# elysium_v0_3.net
KiCad netlist of a schematic drawn in EAGLE
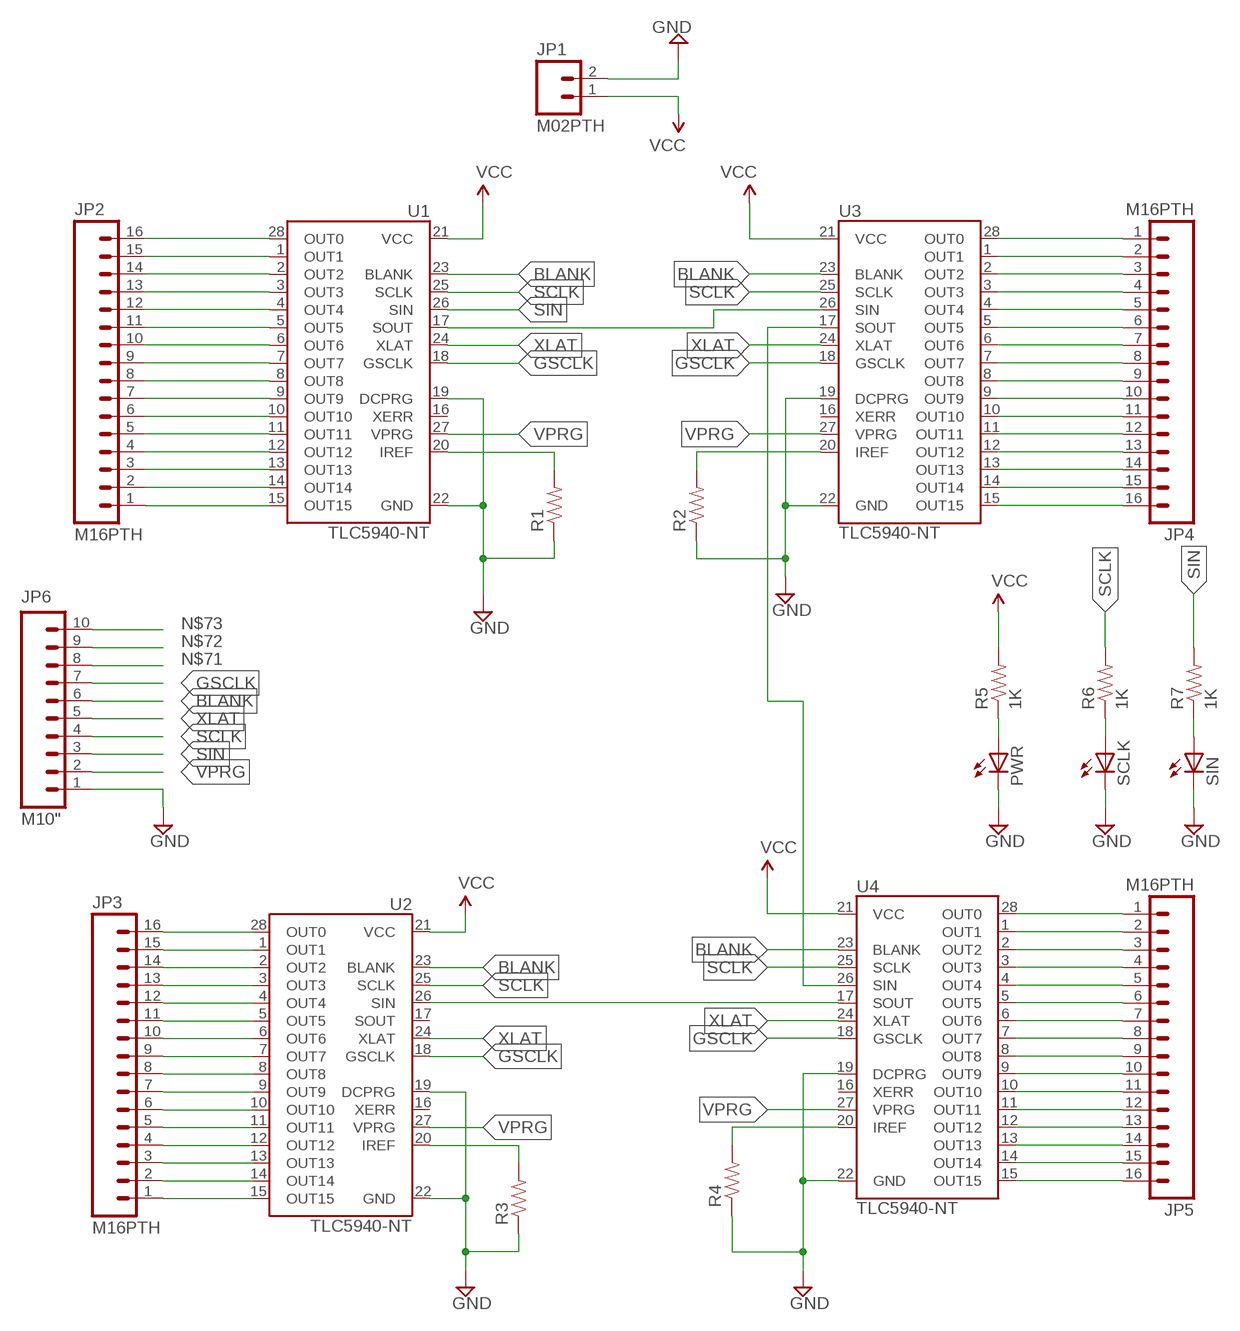
[diagram p0: schematic, sheet 1]

(export (version "E")
  (design (tool "Eeschema 10.0.6"))
  (components
    (comp (ref "JP1")
      (value "M02PTH")
      (footprint "eagle-import:1X02")
      (libsource (lib "eagle-import") (part "M02PTH"))
    )
    (comp (ref "JP2")
      (value "M16PTH")
      (footprint "eagle-import:1X16")
      (libsource (lib "eagle-import") (part "M16PTH"))
    )
    (comp (ref "JP3")
      (value "M16PTH")
      (footprint "eagle-import:1X16")
      (libsource (lib "eagle-import") (part "M16PTH"))
    )
    (comp (ref "JP4")
      (value "M16PTH")
      (footprint "eagle-import:1X16")
      (libsource (lib "eagle-import") (part "M16PTH"))
    )
    (comp (ref "JP5")
      (value "M16PTH")
      (footprint "eagle-import:1X16")
      (libsource (lib "eagle-import") (part "M16PTH"))
    )
    (comp (ref "JP6")
      (value "M10\"")
      (footprint "eagle-import:1X10")
      (libsource (lib "eagle-import") (part "M10{dblquote}"))
    )
    (comp (ref "PWR")
      (value "LED5MM")
      (footprint "eagle-import:LED5MM")
      (libsource (lib "eagle-import") (part "LED5MM"))
    )
    (comp (ref "R1")
      (value "RESISTOREZ")
      (footprint "eagle-import:AXIAL-0.3EZ")
      (libsource (lib "eagle-import") (part "RESISTOREZ"))
    )
    (comp (ref "R2")
      (value "RESISTOREZ")
      (footprint "eagle-import:AXIAL-0.3EZ")
      (libsource (lib "eagle-import") (part "RESISTOREZ"))
    )
    (comp (ref "R3")
      (value "RESISTOREZ")
      (footprint "eagle-import:AXIAL-0.3EZ")
      (libsource (lib "eagle-import") (part "RESISTOREZ"))
    )
    (comp (ref "R4")
      (value "RESISTOREZ")
      (footprint "eagle-import:AXIAL-0.3EZ")
      (libsource (lib "eagle-import") (part "RESISTOREZ"))
    )
    (comp (ref "R5")
      (value "1K")
      (footprint "eagle-import:AXIAL-0.3EZ")
      (libsource (lib "eagle-import") (part "RESISTOREZ"))
    )
    (comp (ref "R6")
      (value "1K")
      (footprint "eagle-import:AXIAL-0.3EZ")
      (libsource (lib "eagle-import") (part "RESISTOREZ"))
    )
    (comp (ref "R7")
      (value "1K")
      (footprint "eagle-import:AXIAL-0.3EZ")
      (libsource (lib "eagle-import") (part "RESISTOREZ"))
    )
    (comp (ref "SCLK")
      (value "LED5MM")
      (footprint "eagle-import:LED5MM")
      (libsource (lib "eagle-import") (part "LED5MM"))
    )
    (comp (ref "SIN")
      (value "LED5MM")
      (footprint "eagle-import:LED5MM")
      (libsource (lib "eagle-import") (part "LED5MM"))
    )
    (comp (ref "U1")
      (value "TLC5940-NT")
      (footprint "eagle-import:DIL28-3")
      (libsource (lib "eagle-import") (part "TLC5940-NT"))
    )
    (comp (ref "U2")
      (value "TLC5940-NT")
      (footprint "eagle-import:DIL28-3")
      (libsource (lib "eagle-import") (part "TLC5940-NT"))
    )
    (comp (ref "U3")
      (value "TLC5940-NT")
      (footprint "eagle-import:DIL28-3")
      (libsource (lib "eagle-import") (part "TLC5940-NT"))
    )
    (comp (ref "U4")
      (value "TLC5940-NT")
      (footprint "eagle-import:DIL28-3")
      (libsource (lib "eagle-import") (part "TLC5940-NT"))
    )
  )
  (nets
    (net (code "1") (name "/N$71") (class "Default")
      (node (ref "JP6") (pin "8") (pinfunction "8_8") (pintype "passive"))
    )
    (net (code "2") (name "/N$72") (class "Default")
      (node (ref "JP6") (pin "9") (pinfunction "9_9") (pintype "passive"))
    )
    (net (code "3") (name "/N$73") (class "Default")
      (node (ref "JP6") (pin "10") (pinfunction "10_10") (pintype "passive"))
    )
    (net (code "4") (name "BLANK") (class "Default")
      (node (ref "JP6") (pin "6") (pinfunction "6_6") (pintype "passive"))
      (node (ref "U1") (pin "23") (pinfunction "BLANK_23") (pintype "bidirectional"))
      (node (ref "U2") (pin "23") (pinfunction "BLANK_23") (pintype "bidirectional"))
      (node (ref "U3") (pin "23") (pinfunction "BLANK_23") (pintype "bidirectional"))
      (node (ref "U4") (pin "23") (pinfunction "BLANK_23") (pintype "bidirectional"))
    )
    (net (code "5") (name "GND") (class "Default")
      (node (ref "JP1") (pin "2") (pinfunction "2_2") (pintype "passive"))
      (node (ref "JP6") (pin "1") (pinfunction "1_1") (pintype "passive"))
      (node (ref "PWR") (pin "K") (pinfunction "C_K") (pintype "passive"))
      (node (ref "R1") (pin "P$1") (pinfunction "1_P$1") (pintype "passive"))
      (node (ref "R2") (pin "P$1") (pinfunction "1_P$1") (pintype "passive"))
      (node (ref "R3") (pin "P$1") (pinfunction "1_P$1") (pintype "passive"))
      (node (ref "R4") (pin "P$1") (pinfunction "1_P$1") (pintype "passive"))
      (node (ref "SCLK") (pin "K") (pinfunction "C_K") (pintype "passive"))
      (node (ref "SIN") (pin "K") (pinfunction "C_K") (pintype "passive"))
      (node (ref "U1") (pin "19") (pinfunction "DCPRG_19") (pintype "bidirectional"))
      (node (ref "U1") (pin "22") (pinfunction "GND_22") (pintype "bidirectional"))
      (node (ref "U2") (pin "19") (pinfunction "DCPRG_19") (pintype "bidirectional"))
      (node (ref "U2") (pin "22") (pinfunction "GND_22") (pintype "bidirectional"))
      (node (ref "U3") (pin "19") (pinfunction "DCPRG_19") (pintype "bidirectional"))
      (node (ref "U3") (pin "22") (pinfunction "GND_22") (pintype "bidirectional"))
      (node (ref "U4") (pin "19") (pinfunction "DCPRG_19") (pintype "bidirectional"))
      (node (ref "U4") (pin "22") (pinfunction "GND_22") (pintype "bidirectional"))
    )
    (net (code "6") (name "GSCLK") (class "Default")
      (node (ref "JP6") (pin "7") (pinfunction "7_7") (pintype "passive"))
      (node (ref "U1") (pin "18") (pinfunction "GSCLK_18") (pintype "bidirectional"))
      (node (ref "U2") (pin "18") (pinfunction "GSCLK_18") (pintype "bidirectional"))
      (node (ref "U3") (pin "18") (pinfunction "GSCLK_18") (pintype "bidirectional"))
      (node (ref "U4") (pin "18") (pinfunction "GSCLK_18") (pintype "bidirectional"))
    )
    (net (code "7") (name "Net-(R1-2)") (class "Default")
      (node (ref "R1") (pin "P$2") (pinfunction "2_P$2") (pintype "passive"))
      (node (ref "U1") (pin "20") (pinfunction "IREF_20") (pintype "bidirectional"))
    )
    (net (code "8") (name "Net-(R2-2)") (class "Default")
      (node (ref "R2") (pin "P$2") (pinfunction "2_P$2") (pintype "passive"))
      (node (ref "U3") (pin "20") (pinfunction "IREF_20") (pintype "bidirectional"))
    )
    (net (code "9") (name "Net-(R3-2)") (class "Default")
      (node (ref "R3") (pin "P$2") (pinfunction "2_P$2") (pintype "passive"))
      (node (ref "U2") (pin "20") (pinfunction "IREF_20") (pintype "bidirectional"))
    )
    (net (code "10") (name "Net-(R4-2)") (class "Default")
      (node (ref "R4") (pin "P$2") (pinfunction "2_P$2") (pintype "passive"))
      (node (ref "U4") (pin "20") (pinfunction "IREF_20") (pintype "bidirectional"))
    )
    (net (code "11") (name "Net-(R5-1)") (class "Default")
      (node (ref "PWR") (pin "A") (pinfunction "A_A") (pintype "passive"))
      (node (ref "R5") (pin "P$1") (pinfunction "1_P$1") (pintype "passive"))
    )
    (net (code "12") (name "Net-(R6-1)") (class "Default")
      (node (ref "R6") (pin "P$1") (pinfunction "1_P$1") (pintype "passive"))
      (node (ref "SCLK") (pin "A") (pinfunction "A_A") (pintype "passive"))
    )
    (net (code "13") (name "Net-(R7-1)") (class "Default")
      (node (ref "R7") (pin "P$1") (pinfunction "1_P$1") (pintype "passive"))
      (node (ref "SIN") (pin "A") (pinfunction "A_A") (pintype "passive"))
    )
    (net (code "14") (name "Net-(U1-OUT0)") (class "Default")
      (node (ref "JP2") (pin "16") (pinfunction "16_16") (pintype "passive"))
      (node (ref "U1") (pin "28") (pinfunction "OUT0_28") (pintype "bidirectional"))
    )
    (net (code "15") (name "Net-(U1-OUT1)") (class "Default")
      (node (ref "JP2") (pin "15") (pinfunction "15_15") (pintype "passive"))
      (node (ref "U1") (pin "1") (pinfunction "OUT1_1") (pintype "bidirectional"))
    )
    (net (code "16") (name "Net-(U1-OUT2)") (class "Default")
      (node (ref "JP2") (pin "14") (pinfunction "14_14") (pintype "passive"))
      (node (ref "U1") (pin "2") (pinfunction "OUT2_2") (pintype "bidirectional"))
    )
    (net (code "17") (name "Net-(U1-OUT3)") (class "Default")
      (node (ref "JP2") (pin "13") (pinfunction "13_13") (pintype "passive"))
      (node (ref "U1") (pin "3") (pinfunction "OUT3_3") (pintype "bidirectional"))
    )
    (net (code "18") (name "Net-(U1-OUT4)") (class "Default")
      (node (ref "JP2") (pin "12") (pinfunction "12_12") (pintype "passive"))
      (node (ref "U1") (pin "4") (pinfunction "OUT4_4") (pintype "bidirectional"))
    )
    (net (code "19") (name "Net-(U1-OUT5)") (class "Default")
      (node (ref "JP2") (pin "11") (pinfunction "11_11") (pintype "passive"))
      (node (ref "U1") (pin "5") (pinfunction "OUT5_5") (pintype "bidirectional"))
    )
    (net (code "20") (name "Net-(U1-OUT6)") (class "Default")
      (node (ref "JP2") (pin "10") (pinfunction "10_10") (pintype "passive"))
      (node (ref "U1") (pin "6") (pinfunction "OUT6_6") (pintype "bidirectional"))
    )
    (net (code "21") (name "Net-(U1-OUT7)") (class "Default")
      (node (ref "JP2") (pin "9") (pinfunction "9_9") (pintype "passive"))
      (node (ref "U1") (pin "7") (pinfunction "OUT7_7") (pintype "bidirectional"))
    )
    (net (code "22") (name "Net-(U1-OUT8)") (class "Default")
      (node (ref "JP2") (pin "8") (pinfunction "8_8") (pintype "passive"))
      (node (ref "U1") (pin "8") (pinfunction "OUT8_8") (pintype "bidirectional"))
    )
    (net (code "23") (name "Net-(U1-OUT9)") (class "Default")
      (node (ref "JP2") (pin "7") (pinfunction "7_7") (pintype "passive"))
      (node (ref "U1") (pin "9") (pinfunction "OUT9_9") (pintype "bidirectional"))
    )
    (net (code "24") (name "Net-(U1-OUT10)") (class "Default")
      (node (ref "JP2") (pin "6") (pinfunction "6_6") (pintype "passive"))
      (node (ref "U1") (pin "10") (pinfunction "OUT10_10") (pintype "bidirectional"))
    )
    (net (code "25") (name "Net-(U1-OUT11)") (class "Default")
      (node (ref "JP2") (pin "5") (pinfunction "5_5") (pintype "passive"))
      (node (ref "U1") (pin "11") (pinfunction "OUT11_11") (pintype "bidirectional"))
    )
    (net (code "26") (name "Net-(U1-OUT12)") (class "Default")
      (node (ref "JP2") (pin "4") (pinfunction "4_4") (pintype "passive"))
      (node (ref "U1") (pin "12") (pinfunction "OUT12_12") (pintype "bidirectional"))
    )
    (net (code "27") (name "Net-(U1-OUT13)") (class "Default")
      (node (ref "JP2") (pin "3") (pinfunction "3_3") (pintype "passive"))
      (node (ref "U1") (pin "13") (pinfunction "OUT13_13") (pintype "bidirectional"))
    )
    (net (code "28") (name "Net-(U1-OUT14)") (class "Default")
      (node (ref "JP2") (pin "2") (pinfunction "2_2") (pintype "passive"))
      (node (ref "U1") (pin "14") (pinfunction "OUT14_14") (pintype "bidirectional"))
    )
    (net (code "29") (name "Net-(U1-OUT15)") (class "Default")
      (node (ref "JP2") (pin "1") (pinfunction "1_1") (pintype "passive"))
      (node (ref "U1") (pin "15") (pinfunction "OUT15_15") (pintype "bidirectional"))
    )
    (net (code "30") (name "Net-(U1-SOUT)") (class "Default")
      (node (ref "U1") (pin "17") (pinfunction "SOUT_17") (pintype "bidirectional"))
      (node (ref "U3") (pin "26") (pinfunction "SIN_26") (pintype "bidirectional"))
    )
    (net (code "31") (name "Net-(U2-OUT0)") (class "Default")
      (node (ref "JP3") (pin "16") (pinfunction "16_16") (pintype "passive"))
      (node (ref "U2") (pin "28") (pinfunction "OUT0_28") (pintype "bidirectional"))
    )
    (net (code "32") (name "Net-(U2-OUT1)") (class "Default")
      (node (ref "JP3") (pin "15") (pinfunction "15_15") (pintype "passive"))
      (node (ref "U2") (pin "1") (pinfunction "OUT1_1") (pintype "bidirectional"))
    )
    (net (code "33") (name "Net-(U2-OUT2)") (class "Default")
      (node (ref "JP3") (pin "14") (pinfunction "14_14") (pintype "passive"))
      (node (ref "U2") (pin "2") (pinfunction "OUT2_2") (pintype "bidirectional"))
    )
    (net (code "34") (name "Net-(U2-OUT3)") (class "Default")
      (node (ref "JP3") (pin "13") (pinfunction "13_13") (pintype "passive"))
      (node (ref "U2") (pin "3") (pinfunction "OUT3_3") (pintype "bidirectional"))
    )
    (net (code "35") (name "Net-(U2-OUT4)") (class "Default")
      (node (ref "JP3") (pin "12") (pinfunction "12_12") (pintype "passive"))
      (node (ref "U2") (pin "4") (pinfunction "OUT4_4") (pintype "bidirectional"))
    )
    (net (code "36") (name "Net-(U2-OUT5)") (class "Default")
      (node (ref "JP3") (pin "11") (pinfunction "11_11") (pintype "passive"))
      (node (ref "U2") (pin "5") (pinfunction "OUT5_5") (pintype "bidirectional"))
    )
    (net (code "37") (name "Net-(U2-OUT6)") (class "Default")
      (node (ref "JP3") (pin "10") (pinfunction "10_10") (pintype "passive"))
      (node (ref "U2") (pin "6") (pinfunction "OUT6_6") (pintype "bidirectional"))
    )
    (net (code "38") (name "Net-(U2-OUT7)") (class "Default")
      (node (ref "JP3") (pin "9") (pinfunction "9_9") (pintype "passive"))
      (node (ref "U2") (pin "7") (pinfunction "OUT7_7") (pintype "bidirectional"))
    )
    (net (code "39") (name "Net-(U2-OUT8)") (class "Default")
      (node (ref "JP3") (pin "8") (pinfunction "8_8") (pintype "passive"))
      (node (ref "U2") (pin "8") (pinfunction "OUT8_8") (pintype "bidirectional"))
    )
    (net (code "40") (name "Net-(U2-OUT9)") (class "Default")
      (node (ref "JP3") (pin "7") (pinfunction "7_7") (pintype "passive"))
      (node (ref "U2") (pin "9") (pinfunction "OUT9_9") (pintype "bidirectional"))
    )
    (net (code "41") (name "Net-(U2-OUT10)") (class "Default")
      (node (ref "JP3") (pin "6") (pinfunction "6_6") (pintype "passive"))
      (node (ref "U2") (pin "10") (pinfunction "OUT10_10") (pintype "bidirectional"))
    )
    (net (code "42") (name "Net-(U2-OUT11)") (class "Default")
      (node (ref "JP3") (pin "5") (pinfunction "5_5") (pintype "passive"))
      (node (ref "U2") (pin "11") (pinfunction "OUT11_11") (pintype "bidirectional"))
    )
    (net (code "43") (name "Net-(U2-OUT12)") (class "Default")
      (node (ref "JP3") (pin "4") (pinfunction "4_4") (pintype "passive"))
      (node (ref "U2") (pin "12") (pinfunction "OUT12_12") (pintype "bidirectional"))
    )
    (net (code "44") (name "Net-(U2-OUT13)") (class "Default")
      (node (ref "JP3") (pin "3") (pinfunction "3_3") (pintype "passive"))
      (node (ref "U2") (pin "13") (pinfunction "OUT13_13") (pintype "bidirectional"))
    )
    (net (code "45") (name "Net-(U2-OUT14)") (class "Default")
      (node (ref "JP3") (pin "2") (pinfunction "2_2") (pintype "passive"))
      (node (ref "U2") (pin "14") (pinfunction "OUT14_14") (pintype "bidirectional"))
    )
    (net (code "46") (name "Net-(U2-OUT15)") (class "Default")
      (node (ref "JP3") (pin "1") (pinfunction "1_1") (pintype "passive"))
      (node (ref "U2") (pin "15") (pinfunction "OUT15_15") (pintype "bidirectional"))
    )
    (net (code "47") (name "Net-(U2-SIN)") (class "Default")
      (node (ref "U2") (pin "26") (pinfunction "SIN_26") (pintype "bidirectional"))
      (node (ref "U4") (pin "17") (pinfunction "SOUT_17") (pintype "bidirectional"))
    )
    (net (code "48") (name "Net-(U3-OUT0)") (class "Default")
      (node (ref "JP4") (pin "1") (pinfunction "1_1") (pintype "passive"))
      (node (ref "U3") (pin "28") (pinfunction "OUT0_28") (pintype "bidirectional"))
    )
    (net (code "49") (name "Net-(U3-OUT1)") (class "Default")
      (node (ref "JP4") (pin "2") (pinfunction "2_2") (pintype "passive"))
      (node (ref "U3") (pin "1") (pinfunction "OUT1_1") (pintype "bidirectional"))
    )
    (net (code "50") (name "Net-(U3-OUT2)") (class "Default")
      (node (ref "JP4") (pin "3") (pinfunction "3_3") (pintype "passive"))
      (node (ref "U3") (pin "2") (pinfunction "OUT2_2") (pintype "bidirectional"))
    )
    (net (code "51") (name "Net-(U3-OUT3)") (class "Default")
      (node (ref "JP4") (pin "4") (pinfunction "4_4") (pintype "passive"))
      (node (ref "U3") (pin "3") (pinfunction "OUT3_3") (pintype "bidirectional"))
    )
    (net (code "52") (name "Net-(U3-OUT4)") (class "Default")
      (node (ref "JP4") (pin "5") (pinfunction "5_5") (pintype "passive"))
      (node (ref "U3") (pin "4") (pinfunction "OUT4_4") (pintype "bidirectional"))
    )
    (net (code "53") (name "Net-(U3-OUT5)") (class "Default")
      (node (ref "JP4") (pin "6") (pinfunction "6_6") (pintype "passive"))
      (node (ref "U3") (pin "5") (pinfunction "OUT5_5") (pintype "bidirectional"))
    )
    (net (code "54") (name "Net-(U3-OUT6)") (class "Default")
      (node (ref "JP4") (pin "7") (pinfunction "7_7") (pintype "passive"))
      (node (ref "U3") (pin "6") (pinfunction "OUT6_6") (pintype "bidirectional"))
    )
    (net (code "55") (name "Net-(U3-OUT7)") (class "Default")
      (node (ref "JP4") (pin "8") (pinfunction "8_8") (pintype "passive"))
      (node (ref "U3") (pin "7") (pinfunction "OUT7_7") (pintype "bidirectional"))
    )
    (net (code "56") (name "Net-(U3-OUT8)") (class "Default")
      (node (ref "JP4") (pin "9") (pinfunction "9_9") (pintype "passive"))
      (node (ref "U3") (pin "8") (pinfunction "OUT8_8") (pintype "bidirectional"))
    )
    (net (code "57") (name "Net-(U3-OUT9)") (class "Default")
      (node (ref "JP4") (pin "10") (pinfunction "10_10") (pintype "passive"))
      (node (ref "U3") (pin "9") (pinfunction "OUT9_9") (pintype "bidirectional"))
    )
    (net (code "58") (name "Net-(U3-OUT10)") (class "Default")
      (node (ref "JP4") (pin "11") (pinfunction "11_11") (pintype "passive"))
      (node (ref "U3") (pin "10") (pinfunction "OUT10_10") (pintype "bidirectional"))
    )
    (net (code "59") (name "Net-(U3-OUT11)") (class "Default")
      (node (ref "JP4") (pin "12") (pinfunction "12_12") (pintype "passive"))
      (node (ref "U3") (pin "11") (pinfunction "OUT11_11") (pintype "bidirectional"))
    )
    (net (code "60") (name "Net-(U3-OUT12)") (class "Default")
      (node (ref "JP4") (pin "13") (pinfunction "13_13") (pintype "passive"))
      (node (ref "U3") (pin "12") (pinfunction "OUT12_12") (pintype "bidirectional"))
    )
    (net (code "61") (name "Net-(U3-OUT13)") (class "Default")
      (node (ref "JP4") (pin "14") (pinfunction "14_14") (pintype "passive"))
      (node (ref "U3") (pin "13") (pinfunction "OUT13_13") (pintype "bidirectional"))
    )
    (net (code "62") (name "Net-(U3-OUT14)") (class "Default")
      (node (ref "JP4") (pin "15") (pinfunction "15_15") (pintype "passive"))
      (node (ref "U3") (pin "14") (pinfunction "OUT14_14") (pintype "bidirectional"))
    )
    (net (code "63") (name "Net-(U3-OUT15)") (class "Default")
      (node (ref "JP4") (pin "16") (pinfunction "16_16") (pintype "passive"))
      (node (ref "U3") (pin "15") (pinfunction "OUT15_15") (pintype "bidirectional"))
    )
    (net (code "64") (name "Net-(U3-SOUT)") (class "Default")
      (node (ref "U3") (pin "17") (pinfunction "SOUT_17") (pintype "bidirectional"))
      (node (ref "U4") (pin "26") (pinfunction "SIN_26") (pintype "bidirectional"))
    )
    (net (code "65") (name "Net-(U4-OUT0)") (class "Default")
      (node (ref "JP5") (pin "1") (pinfunction "1_1") (pintype "passive"))
      (node (ref "U4") (pin "28") (pinfunction "OUT0_28") (pintype "bidirectional"))
    )
    (net (code "66") (name "Net-(U4-OUT1)") (class "Default")
      (node (ref "JP5") (pin "2") (pinfunction "2_2") (pintype "passive"))
      (node (ref "U4") (pin "1") (pinfunction "OUT1_1") (pintype "bidirectional"))
    )
    (net (code "67") (name "Net-(U4-OUT2)") (class "Default")
      (node (ref "JP5") (pin "3") (pinfunction "3_3") (pintype "passive"))
      (node (ref "U4") (pin "2") (pinfunction "OUT2_2") (pintype "bidirectional"))
    )
    (net (code "68") (name "Net-(U4-OUT3)") (class "Default")
      (node (ref "JP5") (pin "4") (pinfunction "4_4") (pintype "passive"))
      (node (ref "U4") (pin "3") (pinfunction "OUT3_3") (pintype "bidirectional"))
    )
    (net (code "69") (name "Net-(U4-OUT4)") (class "Default")
      (node (ref "JP5") (pin "5") (pinfunction "5_5") (pintype "passive"))
      (node (ref "U4") (pin "4") (pinfunction "OUT4_4") (pintype "bidirectional"))
    )
    (net (code "70") (name "Net-(U4-OUT5)") (class "Default")
      (node (ref "JP5") (pin "6") (pinfunction "6_6") (pintype "passive"))
      (node (ref "U4") (pin "5") (pinfunction "OUT5_5") (pintype "bidirectional"))
    )
    (net (code "71") (name "Net-(U4-OUT6)") (class "Default")
      (node (ref "JP5") (pin "7") (pinfunction "7_7") (pintype "passive"))
      (node (ref "U4") (pin "6") (pinfunction "OUT6_6") (pintype "bidirectional"))
    )
    (net (code "72") (name "Net-(U4-OUT7)") (class "Default")
      (node (ref "JP5") (pin "8") (pinfunction "8_8") (pintype "passive"))
      (node (ref "U4") (pin "7") (pinfunction "OUT7_7") (pintype "bidirectional"))
    )
    (net (code "73") (name "Net-(U4-OUT8)") (class "Default")
      (node (ref "JP5") (pin "9") (pinfunction "9_9") (pintype "passive"))
      (node (ref "U4") (pin "8") (pinfunction "OUT8_8") (pintype "bidirectional"))
    )
    (net (code "74") (name "Net-(U4-OUT9)") (class "Default")
      (node (ref "JP5") (pin "10") (pinfunction "10_10") (pintype "passive"))
      (node (ref "U4") (pin "9") (pinfunction "OUT9_9") (pintype "bidirectional"))
    )
    (net (code "75") (name "Net-(U4-OUT10)") (class "Default")
      (node (ref "JP5") (pin "11") (pinfunction "11_11") (pintype "passive"))
      (node (ref "U4") (pin "10") (pinfunction "OUT10_10") (pintype "bidirectional"))
    )
    (net (code "76") (name "Net-(U4-OUT11)") (class "Default")
      (node (ref "JP5") (pin "12") (pinfunction "12_12") (pintype "passive"))
      (node (ref "U4") (pin "11") (pinfunction "OUT11_11") (pintype "bidirectional"))
    )
    (net (code "77") (name "Net-(U4-OUT12)") (class "Default")
      (node (ref "JP5") (pin "13") (pinfunction "13_13") (pintype "passive"))
      (node (ref "U4") (pin "12") (pinfunction "OUT12_12") (pintype "bidirectional"))
    )
    (net (code "78") (name "Net-(U4-OUT13)") (class "Default")
      (node (ref "JP5") (pin "14") (pinfunction "14_14") (pintype "passive"))
      (node (ref "U4") (pin "13") (pinfunction "OUT13_13") (pintype "bidirectional"))
    )
    (net (code "79") (name "Net-(U4-OUT14)") (class "Default")
      (node (ref "JP5") (pin "15") (pinfunction "15_15") (pintype "passive"))
      (node (ref "U4") (pin "14") (pinfunction "OUT14_14") (pintype "bidirectional"))
    )
    (net (code "80") (name "Net-(U4-OUT15)") (class "Default")
      (node (ref "JP5") (pin "16") (pinfunction "16_16") (pintype "passive"))
      (node (ref "U4") (pin "15") (pinfunction "OUT15_15") (pintype "bidirectional"))
    )
    (net (code "81") (name "SCLK") (class "Default")
      (node (ref "JP6") (pin "4") (pinfunction "4_4") (pintype "passive"))
      (node (ref "R6") (pin "P$2") (pinfunction "2_P$2") (pintype "passive"))
      (node (ref "U1") (pin "25") (pinfunction "SCLK_25") (pintype "bidirectional"))
      (node (ref "U2") (pin "25") (pinfunction "SCLK_25") (pintype "bidirectional"))
      (node (ref "U3") (pin "25") (pinfunction "SCLK_25") (pintype "bidirectional"))
      (node (ref "U4") (pin "25") (pinfunction "SCLK_25") (pintype "bidirectional"))
    )
    (net (code "82") (name "SIN") (class "Default")
      (node (ref "JP6") (pin "3") (pinfunction "3_3") (pintype "passive"))
      (node (ref "R7") (pin "P$2") (pinfunction "2_P$2") (pintype "passive"))
      (node (ref "U1") (pin "26") (pinfunction "SIN_26") (pintype "bidirectional"))
    )
    (net (code "83") (name "VCC") (class "Default")
      (node (ref "JP1") (pin "1") (pinfunction "1_1") (pintype "passive"))
      (node (ref "R5") (pin "P$2") (pinfunction "2_P$2") (pintype "passive"))
      (node (ref "U1") (pin "21") (pinfunction "VCC_21") (pintype "bidirectional"))
      (node (ref "U2") (pin "21") (pinfunction "VCC_21") (pintype "bidirectional"))
      (node (ref "U3") (pin "21") (pinfunction "VCC_21") (pintype "bidirectional"))
      (node (ref "U4") (pin "21") (pinfunction "VCC_21") (pintype "bidirectional"))
    )
    (net (code "84") (name "VPRG") (class "Default")
      (node (ref "JP6") (pin "2") (pinfunction "2_2") (pintype "passive"))
      (node (ref "U1") (pin "27") (pinfunction "VPRG_27") (pintype "bidirectional"))
      (node (ref "U2") (pin "27") (pinfunction "VPRG_27") (pintype "bidirectional"))
      (node (ref "U3") (pin "27") (pinfunction "VPRG_27") (pintype "bidirectional"))
      (node (ref "U4") (pin "27") (pinfunction "VPRG_27") (pintype "bidirectional"))
    )
    (net (code "85") (name "XLAT") (class "Default")
      (node (ref "JP6") (pin "5") (pinfunction "5_5") (pintype "passive"))
      (node (ref "U1") (pin "24") (pinfunction "XLAT_24") (pintype "bidirectional"))
      (node (ref "U2") (pin "24") (pinfunction "XLAT_24") (pintype "bidirectional"))
      (node (ref "U3") (pin "24") (pinfunction "XLAT_24") (pintype "bidirectional"))
      (node (ref "U4") (pin "24") (pinfunction "XLAT_24") (pintype "bidirectional"))
    )
    (net (code "86") (name "unconnected-(U1-XERR-Pad16)") (class "Default")
      (node (ref "U1") (pin "16") (pinfunction "XERR_16") (pintype "bidirectional"))
    )
    (net (code "87") (name "unconnected-(U2-SOUT-Pad17)") (class "Default")
      (node (ref "U2") (pin "17") (pinfunction "SOUT_17") (pintype "bidirectional"))
    )
    (net (code "88") (name "unconnected-(U2-XERR-Pad16)") (class "Default")
      (node (ref "U2") (pin "16") (pinfunction "XERR_16") (pintype "bidirectional"))
    )
    (net (code "89") (name "unconnected-(U3-XERR-Pad16)") (class "Default")
      (node (ref "U3") (pin "16") (pinfunction "XERR_16") (pintype "bidirectional"))
    )
    (net (code "90") (name "unconnected-(U4-XERR-Pad16)") (class "Default")
      (node (ref "U4") (pin "16") (pinfunction "XERR_16") (pintype "bidirectional"))
    )
  )
)
